# TPS53319_3_3V_Buck_Converter.net
KiCad netlist of a schematic drawn in Altium Designer
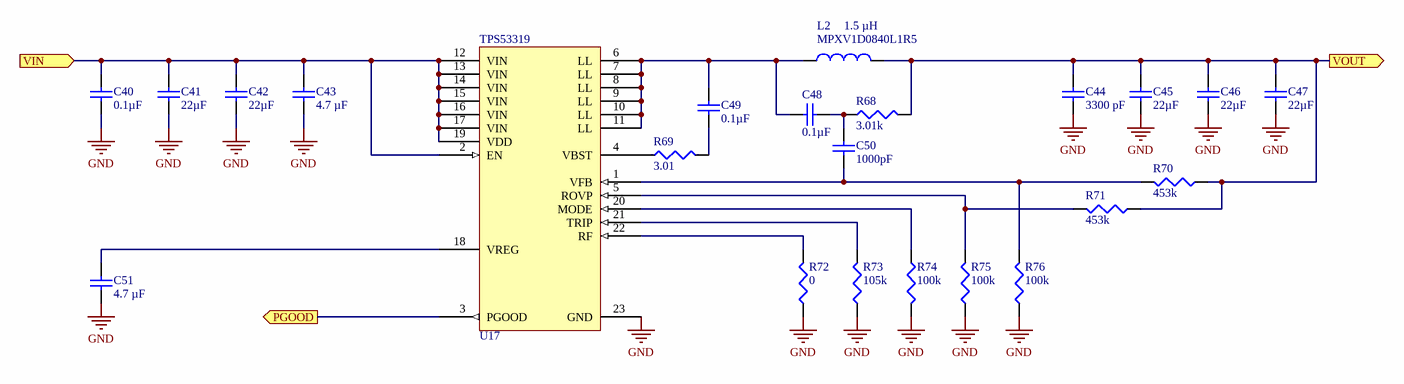
[diagram p0: TPS53319 3.3V Buck Converter.SchDoc]

(export (version "E")
  (design (tool "Eeschema 10.0.6"))
  (components
    (comp (ref "C40")
      (value "0.1µF")
      (footprint "TY-TWK107")
      (description "CAP CER 0.1UF 25V X7R 0306")
      (fields
        (field (name "PART NUMBER") "PC-TY-00817")
        (field (name "MANUFACTURER PART NUMBER") "TWK107B7104MVHT")
        (field (name "PUBLISHER") "AlbertaSat")
      )
      (libsource (lib "Database") (part "Cap"))
    )
    (comp (ref "C41")
      (value "22µF")
      (footprint "TDK-C3225")
      (description "CAP CER 22UF 25V X7R 1210")
      (fields
        (field (name "PART NUMBER") "PC-TDK-02965")
        (field (name "MANUFACTURER PART NUMBER") "C3225X7R1E226M250AB")
        (field (name "PUBLISHER") "AlbertaSat")
      )
      (libsource (lib "Database") (part "Cap"))
    )
    (comp (ref "C42")
      (value "22µF")
      (footprint "TDK-C3225")
      (description "CAP CER 22UF 25V X7R 1210")
      (fields
        (field (name "PART NUMBER") "PC-TDK-02965")
        (field (name "MANUFACTURER PART NUMBER") "C3225X7R1E226M250AB")
        (field (name "PUBLISHER") "AlbertaSat")
      )
      (libsource (lib "Database") (part "Cap"))
    )
    (comp (ref "C43")
      (value "4.7 µF")
      (footprint "MUR-GRM188")
      (description "CAP CER 4.7UF 16V X7R 0603")
      (fields
        (field (name "PART NUMBER") "10165")
        (field (name "MANUFACTURER PART NUMBER") "GRM188Z71C475KE21D")
        (field (name "PUBLISHER") "Altium Limited")
      )
      (libsource (lib "Database") (part "Cap"))
    )
    (comp (ref "C44")
      (value "3300 pF")
      (footprint "KEM-0402BB")
      (description "CAP CER 3300PF 50V X7R 0402")
      (fields
        (field (name "PART NUMBER") "PC-KEM-03166")
        (field (name "MANUFACTURER PART NUMBER") "C0402C332K5RAC7867")
        (field (name "PUBLISHER") "AlbertaSat")
      )
      (libsource (lib "Database") (part "Cap"))
    )
    (comp (ref "C45")
      (value "22µF")
      (footprint "TDK-C3225")
      (description "CAP CER 22UF 25V X7R 1210")
      (fields
        (field (name "PART NUMBER") "PC-TDK-02965")
        (field (name "MANUFACTURER PART NUMBER") "C3225X7R1E226M250AB")
        (field (name "PUBLISHER") "AlbertaSat")
      )
      (libsource (lib "Database") (part "Cap"))
    )
    (comp (ref "C46")
      (value "22µF")
      (footprint "TDK-C3225")
      (description "CAP CER 22UF 25V X7R 1210")
      (fields
        (field (name "PART NUMBER") "PC-TDK-02965")
        (field (name "MANUFACTURER PART NUMBER") "C3225X7R1E226M250AB")
        (field (name "PUBLISHER") "AlbertaSat")
      )
      (libsource (lib "Database") (part "Cap"))
    )
    (comp (ref "C47")
      (value "22µF")
      (footprint "TDK-C3225")
      (description "CAP CER 22UF 25V X7R 1210")
      (fields
        (field (name "PART NUMBER") "PC-TDK-02965")
        (field (name "MANUFACTURER PART NUMBER") "C3225X7R1E226M250AB")
        (field (name "PUBLISHER") "AlbertaSat")
      )
      (libsource (lib "Database") (part "Cap"))
    )
    (comp (ref "C48")
      (value "0.1µF")
      (footprint "TY-TWK107")
      (description "CAP CER 0.1UF 25V X7R 0306")
      (fields
        (field (name "PART NUMBER") "PC-TY-00817")
        (field (name "MANUFACTURER PART NUMBER") "TWK107B7104MVHT")
        (field (name "PUBLISHER") "AlbertaSat")
      )
      (libsource (lib "Database") (part "Cap"))
    )
    (comp (ref "C49")
      (value "0.1µF")
      (footprint "TY-TWK107")
      (description "CAP CER 0.1UF 25V X7R 0306")
      (fields
        (field (name "PART NUMBER") "PC-TY-00817")
        (field (name "MANUFACTURER PART NUMBER") "TWK107B7104MVHT")
        (field (name "PUBLISHER") "AlbertaSat")
      )
      (libsource (lib "Database") (part "Cap"))
    )
    (comp (ref "C50")
      (value "1000pF")
      (footprint "TDK-CGA2B")
      (description "CAP CER 1000PF 100V C0G 0402")
      (fields
        (field (name "PART NUMBER") "PC-TDK-01454")
        (field (name "MANUFACTURER PART NUMBER") "CGA2B1C0G2A102J050BC")
        (field (name "PUBLISHER") "AlbertaSat")
      )
      (libsource (lib "Database") (part "Cap"))
    )
    (comp (ref "C51")
      (value "4.7 µF")
      (footprint "MUR-GRM188")
      (description "CAP CER 4.7UF 16V X7R 0603")
      (fields
        (field (name "PART NUMBER") "10165")
        (field (name "MANUFACTURER PART NUMBER") "GRM188Z71C475KE21D")
        (field (name "PUBLISHER") "Altium Limited")
      )
      (libsource (lib "Database") (part "Cap"))
    )
    (comp (ref "L2")
      (value "1.5 µH")
      (footprint "KEM-MPXV1D0840")
      (description "FIXED IND 1.5UH 16.2A 6.8MOHM SM")
      (fields
        (field (name "PART NUMBER") "PL-KEM-03165")
        (field (name "MANUFACTURER PART NUMBER") "MPXV1D0840L1R5")
        (field (name "TOLERANCE") "±20%")
        (field (name "PUBLISHER") "AlbertaSat")
      )
      (libsource (lib "Database") (part "Inductor"))
    )
    (comp (ref "R68")
      (value "3.01k")
      (footprint "VSH-CRCW0201")
      (description "RES SMD 3.01K OHM 1% 1/20W 0201")
      (fields
        (field (name "PART NUMBER") "PR-VSH-00325")
        (field (name "MANUFACTURER PART NUMBER") "CRCW02013K01FKED")
        (field (name "PUBLISHER") "AlbertaSat")
      )
      (libsource (lib "Database") (part "Res3"))
    )
    (comp (ref "R69")
      (value "3.01")
      (footprint "VSH-CRCW0201")
      (description "CRCW0201 - 200/+400 3R01 1% ET7")
      (fields
        (field (name "PART NUMBER") "PR-VSH-00326")
        (field (name "MANUFACTURER PART NUMBER") "CRCW02013R01FXED")
        (field (name "PUBLISHER") "AlbertaSat")
      )
      (libsource (lib "Database") (part "Res3"))
    )
    (comp (ref "R70")
      (value "453k")
      (footprint "PANA-ERJ2R")
      (description "RES SMD 453K OHM 1% 1/10W 0402")
      (fields
        (field (name "PART NUMBER") "19391")
        (field (name "MANUFACTURER PART NUMBER") "ERJ-2RKF4533X")
        (field (name "PUBLISHER") "Altium Limited")
      )
      (libsource (lib "Database") (part "Res3"))
    )
    (comp (ref "R71")
      (value "453k")
      (footprint "PANA-ERJ2R")
      (description "RES SMD 453K OHM 1% 1/10W 0402")
      (fields
        (field (name "PART NUMBER") "19391")
        (field (name "MANUFACTURER PART NUMBER") "ERJ-2RKF4533X")
        (field (name "PUBLISHER") "Altium Limited")
      )
      (libsource (lib "Database") (part "Res3"))
    )
    (comp (ref "R72")
      (value "0")
      (footprint "PANA-ERJ2G")
      (description "RES SMD 0.0OHM JUMPER 1/10W 0402")
      (fields (field (name "PART NUMBER") "13127") (field (name "MANUFACTURER PART NUMBER") "ERJ-2GE0R00X"))
      (libsource (lib "Database") (part "Jumper3"))
    )
    (comp (ref "R73")
      (value "105k")
      (footprint "PANA-ERJ2R")
      (description "RES SMD 105K OHM 1% 1/10W 0402")
      (fields
        (field (name "PART NUMBER") "18767")
        (field (name "MANUFACTURER PART NUMBER") "ERJ-2RKF1053X")
        (field (name "PUBLISHER") "Altium Limited")
      )
      (libsource (lib "Database") (part "Res3"))
    )
    (comp (ref "R74")
      (value "100k")
      (footprint "PANA-ERJ2R")
      (description "RES SMD 100K OHM 1% 1/10W 0402")
      (fields
        (field (name "PART NUMBER") "18739")
        (field (name "MANUFACTURER PART NUMBER") "ERJ-2RKF1003X")
        (field (name "PUBLISHER") "Altium Limited")
      )
      (libsource (lib "Database") (part "Res3"))
    )
    (comp (ref "R75")
      (value "100k")
      (footprint "PANA-ERJ2R")
      (description "RES SMD 100K OHM 1% 1/10W 0402")
      (fields
        (field (name "PART NUMBER") "18739")
        (field (name "MANUFACTURER PART NUMBER") "ERJ-2RKF1003X")
        (field (name "PUBLISHER") "Altium Limited")
      )
      (libsource (lib "Database") (part "Res3"))
    )
    (comp (ref "R76")
      (value "100k")
      (footprint "PANA-ERJ2R")
      (description "RES SMD 100K OHM 1% 1/10W 0402")
      (fields
        (field (name "PART NUMBER") "18739")
        (field (name "MANUFACTURER PART NUMBER") "ERJ-2RKF1003X")
        (field (name "PUBLISHER") "Altium Limited")
      )
      (libsource (lib "Database") (part "Res3"))
    )
    (comp (ref "U17")
      (value "TPS53319")
      (footprint "TI-R-PSON-N22")
      (description "IC REG BUCK ADJUSTABLE 14A 22SON")
      (fields (field (name "PART NUMBER") "145") (field (name "MANUFACTURER PART NUMBER") "TPS53319DQPT"))
      (libsource (lib "Database") (part "TPS53319DQPT"))
    )
  )
  (nets
    (net (code "1") (name "/PGOOD") (class "Default")
      (node (ref "U17") (pin "3") (pinfunction "PGOOD_3") (pintype "output"))
    )
    (net (code "2") (name "/VIN") (class "Default")
      (node (ref "C40") (pin "2") (pinfunction "2_2") (pintype "passive"))
      (node (ref "C41") (pin "2") (pinfunction "2_2") (pintype "passive"))
      (node (ref "C42") (pin "2") (pinfunction "2_2") (pintype "passive"))
      (node (ref "C43") (pin "2") (pinfunction "2_2") (pintype "passive"))
      (node (ref "U17") (pin "12") (pinfunction "VIN_12") (pintype "power_in"))
      (node (ref "U17") (pin "13") (pinfunction "VIN_13") (pintype "power_in"))
      (node (ref "U17") (pin "14") (pinfunction "VIN_14") (pintype "power_in"))
      (node (ref "U17") (pin "15") (pinfunction "VIN_15") (pintype "power_in"))
      (node (ref "U17") (pin "16") (pinfunction "VIN_16") (pintype "power_in"))
      (node (ref "U17") (pin "17") (pinfunction "VIN_17") (pintype "power_in"))
      (node (ref "U17") (pin "19") (pinfunction "VDD_19") (pintype "power_in"))
      (node (ref "U17") (pin "2") (pinfunction "EN_2") (pintype "input"))
    )
    (net (code "3") (name "/VOUT") (class "Default")
      (node (ref "C44") (pin "2") (pinfunction "2_2") (pintype "passive"))
      (node (ref "C45") (pin "2") (pinfunction "2_2") (pintype "passive"))
      (node (ref "C46") (pin "2") (pinfunction "2_2") (pintype "passive"))
      (node (ref "C47") (pin "2") (pinfunction "2_2") (pintype "passive"))
      (node (ref "L2") (pin "2") (pinfunction "2_2") (pintype "passive"))
      (node (ref "R68") (pin "2") (pinfunction "2_2") (pintype "passive"))
      (node (ref "R70") (pin "1") (pinfunction "1_1") (pintype "passive"))
      (node (ref "R71") (pin "1") (pinfunction "1_1") (pintype "passive"))
    )
    (net (code "4") (name "GND") (class "Default")
      (node (ref "C40") (pin "1") (pinfunction "1_1") (pintype "passive"))
      (node (ref "C41") (pin "1") (pinfunction "1_1") (pintype "passive"))
      (node (ref "C42") (pin "1") (pinfunction "1_1") (pintype "passive"))
      (node (ref "C43") (pin "1") (pinfunction "1_1") (pintype "passive"))
      (node (ref "C44") (pin "1") (pinfunction "1_1") (pintype "passive"))
      (node (ref "C45") (pin "1") (pinfunction "1_1") (pintype "passive"))
      (node (ref "C46") (pin "1") (pinfunction "1_1") (pintype "passive"))
      (node (ref "C47") (pin "1") (pinfunction "1_1") (pintype "passive"))
      (node (ref "C51") (pin "1") (pinfunction "1_1") (pintype "passive"))
      (node (ref "R72") (pin "1") (pinfunction "1_1") (pintype "passive"))
      (node (ref "R73") (pin "1") (pinfunction "1_1") (pintype "passive"))
      (node (ref "R74") (pin "1") (pinfunction "1_1") (pintype "passive"))
      (node (ref "R75") (pin "1") (pinfunction "1_1") (pintype "passive"))
      (node (ref "R76") (pin "1") (pinfunction "1_1") (pintype "passive"))
      (node (ref "U17") (pin "23") (pinfunction "GND_23") (pintype "power_in"))
    )
    (net (code "5") (name "Net-(C48-Pad1)") (class "Default")
      (node (ref "C48") (pin "1") (pinfunction "1_1") (pintype "passive"))
      (node (ref "C50") (pin "1") (pinfunction "1_1") (pintype "passive"))
      (node (ref "R68") (pin "1") (pinfunction "1_1") (pintype "passive"))
    )
    (net (code "6") (name "Net-(C48-Pad2)") (class "Default")
      (node (ref "C48") (pin "2") (pinfunction "2_2") (pintype "passive"))
      (node (ref "C49") (pin "2") (pinfunction "2_2") (pintype "passive"))
      (node (ref "L2") (pin "1") (pinfunction "1_1") (pintype "passive"))
      (node (ref "U17") (pin "10") (pinfunction "LL_10") (pintype "power_in"))
      (node (ref "U17") (pin "11") (pinfunction "LL_11") (pintype "power_in"))
      (node (ref "U17") (pin "6") (pinfunction "LL_6") (pintype "power_in"))
      (node (ref "U17") (pin "7") (pinfunction "LL_7") (pintype "power_in"))
      (node (ref "U17") (pin "8") (pinfunction "LL_8") (pintype "power_in"))
      (node (ref "U17") (pin "9") (pinfunction "LL_9") (pintype "power_in"))
    )
    (net (code "7") (name "Net-(C49-Pad1)") (class "Default")
      (node (ref "C49") (pin "1") (pinfunction "1_1") (pintype "passive"))
      (node (ref "R69") (pin "2") (pinfunction "2_2") (pintype "passive"))
    )
    (net (code "8") (name "Net-(U17-MODE)") (class "Default")
      (node (ref "R74") (pin "2") (pinfunction "2_2") (pintype "passive"))
      (node (ref "U17") (pin "20") (pinfunction "MODE_20") (pintype "input"))
    )
    (net (code "9") (name "Net-(U17-RF)") (class "Default")
      (node (ref "R72") (pin "2") (pinfunction "2_2") (pintype "passive"))
      (node (ref "U17") (pin "22") (pinfunction "RF_22") (pintype "input"))
    )
    (net (code "10") (name "Net-(U17-ROVP)") (class "Default")
      (node (ref "R71") (pin "2") (pinfunction "2_2") (pintype "passive"))
      (node (ref "R75") (pin "2") (pinfunction "2_2") (pintype "passive"))
      (node (ref "U17") (pin "5") (pinfunction "ROVP_5") (pintype "input"))
    )
    (net (code "11") (name "Net-(U17-TRIP)") (class "Default")
      (node (ref "R73") (pin "2") (pinfunction "2_2") (pintype "passive"))
      (node (ref "U17") (pin "21") (pinfunction "TRIP_21") (pintype "input"))
    )
    (net (code "12") (name "Net-(U17-VBST)") (class "Default")
      (node (ref "R69") (pin "1") (pinfunction "1_1") (pintype "passive"))
      (node (ref "U17") (pin "4") (pinfunction "VBST_4") (pintype "power_in"))
    )
    (net (code "13") (name "Net-(U17-VFB)") (class "Default")
      (node (ref "C50") (pin "2") (pinfunction "2_2") (pintype "passive"))
      (node (ref "R70") (pin "2") (pinfunction "2_2") (pintype "passive"))
      (node (ref "R76") (pin "2") (pinfunction "2_2") (pintype "passive"))
      (node (ref "U17") (pin "1") (pinfunction "VFB_1") (pintype "input"))
    )
    (net (code "14") (name "Net-(U17-VREG)") (class "Default")
      (node (ref "C51") (pin "2") (pinfunction "2_2") (pintype "passive"))
      (node (ref "U17") (pin "18") (pinfunction "VREG_18") (pintype "passive"))
    )
  )
)
